# LaunchpadStepperXY.net
KiCad netlist of a schematic drawn in Altium Designer
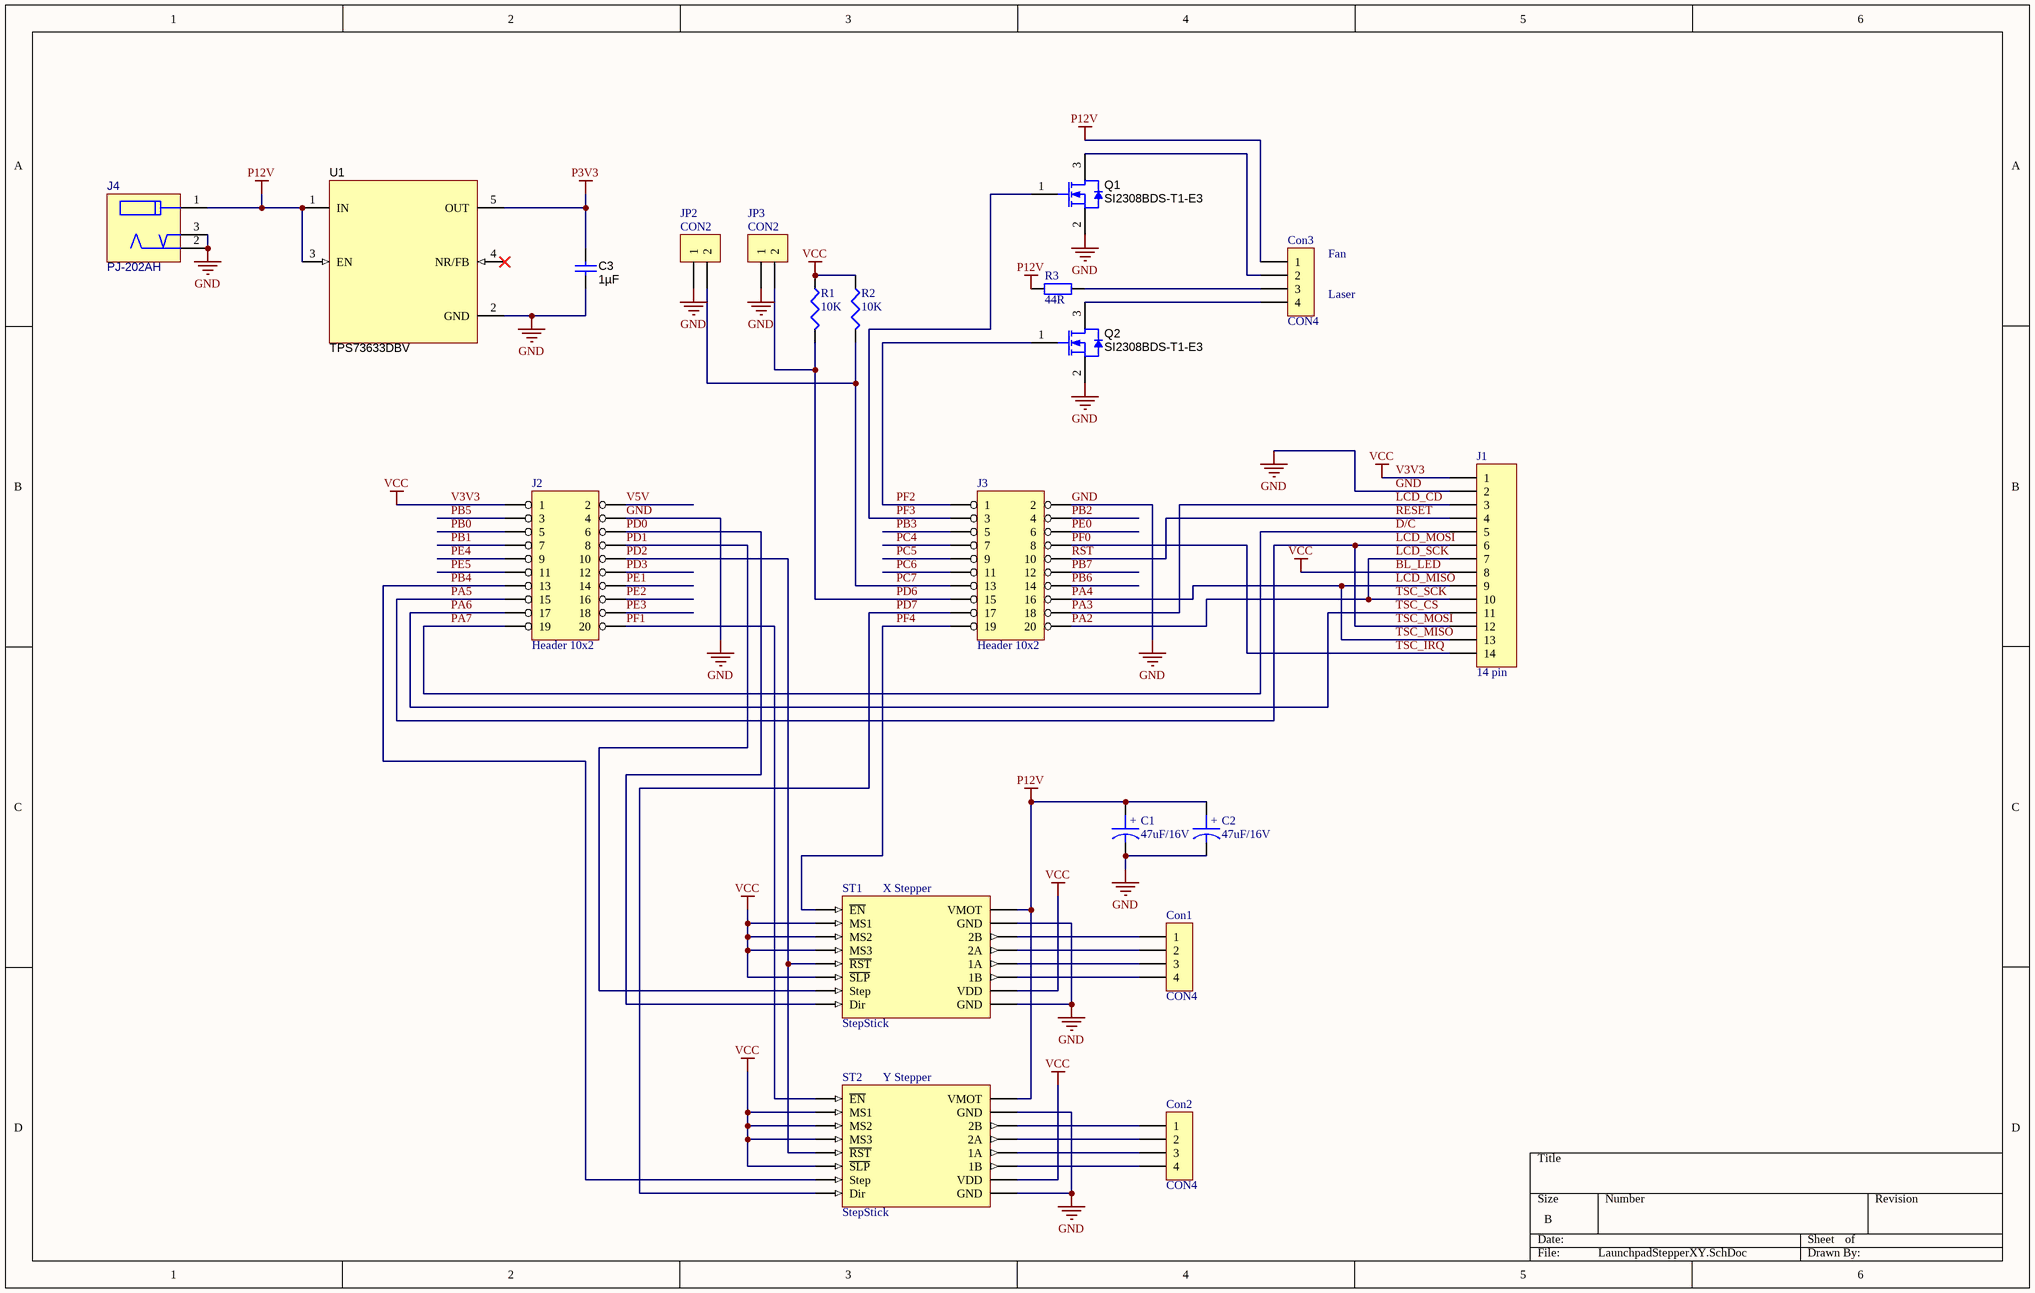
[diagram p0: LaunchpadStepperXY.SchDoc]

(export (version "E")
  (design (tool "Eeschema 10.0.6"))
  (components
    (comp (ref "C1")
      (value "47uF/16V")
      (footprint "PanasonicD")
      (description "Polarized Capacitor")
      (fields (field (name "MANUFACTURER") "Panasonic"))
      (libsource (lib "*") (part "C_POL"))
    )
    (comp (ref "C2")
      (value "47uF/16V")
      (footprint "PanasonicD")
      (description "Polarized Capacitor")
      (fields (field (name "MANUFACTURER") "Panasonic"))
      (libsource (lib "*") (part "C_POL"))
    )
    (comp (ref "C3")
      (value "UMK107AB7105KA-T")
      (footprint "0603")
      (description "CAP, CERM, 1 µF, 50 V, +/- 10%, X7R, 0603")
      (fields
        (field (name "VALUEDISPLAYED") "1µF")
        (field (name "MANUFACTURER") "Taiyo Yuden")
        (field (name "PUBLISHER") "Texas Instruments")
      )
      (libsource (lib "Capacitor_Ceramic") (part "UMK107AB7105KA-T"))
    )
    (comp (ref "Con1") (value "CON4") (footprint "SIP4") (libsource (lib "Steve") (part "CON4")))
    (comp (ref "Con2") (value "CON4") (footprint "SIP4") (libsource (lib "Steve") (part "CON4")))
    (comp (ref "Con3") (value "CON4") (footprint "SIP4") (libsource (lib "Steve") (part "CON4")))
    (comp (ref "J1")
      (value "14 pin")
      (footprint "SIP14")
      (description "Connector")
      (libsource (lib "Steve") (part "CON14"))
    )
    (comp (ref "J2") (value "Header 10x2") (footprint "IDC20") (libsource (lib "Steve") (part "Header 10x2")))
    (comp (ref "J3") (value "Header 10x2") (footprint "IDC20") (libsource (lib "Steve") (part "Header 10x2")))
    (comp (ref "J4")
      (value "PJ-202AH")
      (footprint "CONN_CUI-PJ-202AH")
      (description "Connector, DC Jack 2.1X5.5 mm, TH")
      (fields
        (field (name "MANUFACTURER") "CUI Inc.")
        (field (name "SYMBOLCREATOR") "a0799628")
        (field (name "PUBLISHER") "Texas Instruments")
      )
      (libsource (lib "Connectors_Other") (part "PJ-202AH"))
    )
    (comp (ref "JP2")
      (value "CON2")
      (footprint "SIP2")
      (description "Connector")
      (libsource (lib "Steve") (part "CON2"))
    )
    (comp (ref "JP3")
      (value "CON2")
      (footprint "SIP2")
      (description "Connector")
      (libsource (lib "Steve") (part "CON2"))
    )
    (comp (ref "Q1")
      (value "SI2308BDS-T1-E3")
      (footprint "SOT-23")
      (description "MOSFET, N-CH, 60 V, 2.3 A, SOT-23")
      (fields (field (name "MANUFACTURER") "Vishay-Siliconix") (field (name "PUBLISHER") "Texas Instruments"))
      (libsource (lib "FETs") (part "SI2308BDS-T1-E3"))
    )
    (comp (ref "Q2")
      (value "SI2308BDS-T1-E3")
      (footprint "SOT-23")
      (description "MOSFET, N-CH, 60 V, 2.3 A, SOT-23")
      (fields (field (name "MANUFACTURER") "Vishay-Siliconix") (field (name "PUBLISHER") "Texas Instruments"))
      (libsource (lib "FETs") (part "SI2308BDS-T1-E3"))
    )
    (comp (ref "R1")
      (value "10K")
      (footprint "0603")
      (description "Resistor")
      (libsource (lib "Steve") (part "RES"))
    )
    (comp (ref "R2")
      (value "10K")
      (footprint "0603")
      (description "Resistor")
      (libsource (lib "Steve") (part "RES"))
    )
    (comp (ref "R3")
      (value "44R")
      (footprint "AXIAL-0.4")
      (description "Resistor")
      (fields (field (name "PUBLISHER") "Altium Limited"))
      (libsource (lib "Miscellaneous Devices") (part "Res2"))
    )
    (comp (ref "ST1")
      (value "StepStick")
      (footprint "StepStick")
      (description "Connector")
      (libsource (lib "Steve") (part "CON14_1"))
    )
    (comp (ref "ST2")
      (value "StepStick")
      (footprint "StepStick")
      (description "Connector")
      (libsource (lib "Steve") (part "CON14_1"))
    )
    (comp (ref "U1")
      (value "TPS73633DBV")
      (footprint "DBV0005A_N")
      (description "Cap-Free, NMOS, 400mA Low-Dropout Regulator with Reverse Current Protection, DBV0005A")
      (fields
        (field (name "MANUFACTURER") "Texas Instruments")
        (field (name "SYMBOLCREATOR") "a0411947")
        (field (name "PUBLISHER") "Texas Instruments")
      )
      (libsource (lib "TI_Pre_Release") (part "TPS73633DBV"))
    )
  )
  (nets
    (net (code "1") (name "/D{slash}C") (class "Default")
      (node (ref "J1") (pin "5") (pinfunction "5_5") (pintype "passive"))
      (node (ref "J2") (pin "19") (pinfunction "19_19") (pintype "passive"))
    )
    (net (code "2") (name "/LCD_CD") (class "Default")
      (node (ref "J1") (pin "3") (pinfunction "3_3") (pintype "passive"))
      (node (ref "J3") (pin "18") (pinfunction "18_18") (pintype "passive"))
    )
    (net (code "3") (name "/LCD_MISO") (class "Default")
      (node (ref "J1") (pin "13") (pinfunction "13_13") (pintype "passive"))
      (node (ref "J1") (pin "9") (pinfunction "9_9") (pintype "passive"))
      (node (ref "J3") (pin "16") (pinfunction "16_16") (pintype "passive"))
    )
    (net (code "4") (name "/LCD_MOSI") (class "Default")
      (node (ref "J1") (pin "12") (pinfunction "12_12") (pintype "passive"))
      (node (ref "J1") (pin "6") (pinfunction "6_6") (pintype "passive"))
      (node (ref "J2") (pin "15") (pinfunction "15_15") (pintype "passive"))
    )
    (net (code "5") (name "/LCD_SCK") (class "Default")
      (node (ref "J1") (pin "10") (pinfunction "10_10") (pintype "passive"))
      (node (ref "J1") (pin "7") (pinfunction "7_7") (pintype "passive"))
      (node (ref "J3") (pin "20") (pinfunction "20_20") (pintype "passive"))
    )
    (net (code "6") (name "/PA6") (class "Default")
      (node (ref "J1") (pin "11") (pinfunction "11_11") (pintype "passive"))
      (node (ref "J2") (pin "17") (pinfunction "17_17") (pintype "passive"))
    )
    (net (code "7") (name "/PB0") (class "Default")
      (node (ref "J2") (pin "5") (pinfunction "5_5") (pintype "passive"))
    )
    (net (code "8") (name "/PB1") (class "Default")
      (node (ref "J2") (pin "7") (pinfunction "7_7") (pintype "passive"))
    )
    (net (code "9") (name "/PB2") (class "Default")
      (node (ref "J3") (pin "4") (pinfunction "4_4") (pintype "passive"))
    )
    (net (code "10") (name "/PB3") (class "Default")
      (node (ref "J3") (pin "5") (pinfunction "5_5") (pintype "passive"))
    )
    (net (code "11") (name "/PB4") (class "Default")
      (node (ref "J2") (pin "13") (pinfunction "13_13") (pintype "passive"))
      (node (ref "ST2") (pin "7") (pinfunction "Step_7") (pintype "input"))
    )
    (net (code "12") (name "/PB5") (class "Default")
      (node (ref "J2") (pin "3") (pinfunction "3_3") (pintype "passive"))
    )
    (net (code "13") (name "/PB6") (class "Default")
      (node (ref "J3") (pin "14") (pinfunction "14_14") (pintype "passive"))
    )
    (net (code "14") (name "/PB7") (class "Default")
      (node (ref "J3") (pin "12") (pinfunction "12_12") (pintype "passive"))
    )
    (net (code "15") (name "/PC4") (class "Default")
      (node (ref "J3") (pin "7") (pinfunction "7_7") (pintype "passive"))
    )
    (net (code "16") (name "/PC5") (class "Default")
      (node (ref "J3") (pin "9") (pinfunction "9_9") (pintype "passive"))
    )
    (net (code "17") (name "/PC6") (class "Default")
      (node (ref "J3") (pin "11") (pinfunction "11_11") (pintype "passive"))
    )
    (net (code "18") (name "/PC7") (class "Default")
      (node (ref "J3") (pin "13") (pinfunction "13_13") (pintype "passive"))
      (node (ref "JP2") (pin "2") (pinfunction "2_2") (pintype "passive"))
      (node (ref "R2") (pin "2") (pinfunction "2_2") (pintype "passive"))
    )
    (net (code "19") (name "/PD0") (class "Default")
      (node (ref "J2") (pin "6") (pinfunction "6_6") (pintype "passive"))
      (node (ref "ST1") (pin "8") (pinfunction "Dir_8") (pintype "input"))
    )
    (net (code "20") (name "/PD1") (class "Default")
      (node (ref "J2") (pin "8") (pinfunction "8_8") (pintype "passive"))
      (node (ref "ST1") (pin "7") (pinfunction "Step_7") (pintype "input"))
    )
    (net (code "21") (name "/PD2") (class "Default")
      (node (ref "J2") (pin "10") (pinfunction "10_10") (pintype "passive"))
      (node (ref "ST1") (pin "5") (pinfunction "~{RST}_5") (pintype "input"))
      (node (ref "ST2") (pin "5") (pinfunction "~{RST}_5") (pintype "input"))
    )
    (net (code "22") (name "/PD3") (class "Default")
      (node (ref "J2") (pin "12") (pinfunction "12_12") (pintype "passive"))
    )
    (net (code "23") (name "/PD6") (class "Default")
      (node (ref "J3") (pin "15") (pinfunction "15_15") (pintype "passive"))
      (node (ref "JP3") (pin "2") (pinfunction "2_2") (pintype "passive"))
      (node (ref "R1") (pin "2") (pinfunction "2_2") (pintype "passive"))
    )
    (net (code "24") (name "/PD7") (class "Default")
      (node (ref "J3") (pin "17") (pinfunction "17_17") (pintype "passive"))
      (node (ref "ST2") (pin "8") (pinfunction "Dir_8") (pintype "input"))
    )
    (net (code "25") (name "/PE0") (class "Default")
      (node (ref "J3") (pin "6") (pinfunction "6_6") (pintype "passive"))
    )
    (net (code "26") (name "/PE1") (class "Default")
      (node (ref "J2") (pin "14") (pinfunction "14_14") (pintype "passive"))
    )
    (net (code "27") (name "/PE2") (class "Default")
      (node (ref "J2") (pin "16") (pinfunction "16_16") (pintype "passive"))
    )
    (net (code "28") (name "/PE3") (class "Default")
      (node (ref "J2") (pin "18") (pinfunction "18_18") (pintype "passive"))
    )
    (net (code "29") (name "/PE4") (class "Default")
      (node (ref "J2") (pin "9") (pinfunction "9_9") (pintype "passive"))
    )
    (net (code "30") (name "/PE5") (class "Default")
      (node (ref "J2") (pin "11") (pinfunction "11_11") (pintype "passive"))
    )
    (net (code "31") (name "/PF0") (class "Default")
      (node (ref "J1") (pin "14") (pinfunction "14_14") (pintype "passive"))
      (node (ref "J3") (pin "8") (pinfunction "8_8") (pintype "passive"))
    )
    (net (code "32") (name "/PF1") (class "Default")
      (node (ref "J2") (pin "20") (pinfunction "20_20") (pintype "passive"))
      (node (ref "ST2") (pin "1") (pinfunction "~{EN}_1") (pintype "input"))
    )
    (net (code "33") (name "/PF2") (class "Default")
      (node (ref "J3") (pin "1") (pinfunction "1_1") (pintype "passive"))
      (node (ref "Q2") (pin "1") (pinfunction "G_1") (pintype "passive"))
    )
    (net (code "34") (name "/PF3") (class "Default")
      (node (ref "J3") (pin "3") (pinfunction "3_3") (pintype "passive"))
      (node (ref "Q1") (pin "1") (pinfunction "G_1") (pintype "passive"))
    )
    (net (code "35") (name "/PF4") (class "Default")
      (node (ref "J3") (pin "19") (pinfunction "19_19") (pintype "passive"))
      (node (ref "ST1") (pin "1") (pinfunction "~{EN}_1") (pintype "input"))
    )
    (net (code "36") (name "/V5V") (class "Default")
      (node (ref "J2") (pin "2") (pinfunction "2_2") (pintype "passive"))
    )
    (net (code "37") (name "/~{RESET}") (class "Default")
      (node (ref "J1") (pin "4") (pinfunction "4_4") (pintype "passive"))
      (node (ref "J3") (pin "10") (pinfunction "10_10") (pintype "passive"))
    )
    (net (code "38") (name "GND") (class "Default")
      (node (ref "C1") (pin "2") (pinfunction "2_2") (pintype "passive"))
      (node (ref "C2") (pin "2") (pinfunction "2_2") (pintype "passive"))
      (node (ref "C3") (pin "2") (pinfunction "2_2") (pintype "passive"))
      (node (ref "J1") (pin "2") (pinfunction "2_2") (pintype "passive"))
      (node (ref "J2") (pin "4") (pinfunction "4_4") (pintype "passive"))
      (node (ref "J3") (pin "2") (pinfunction "2_2") (pintype "passive"))
      (node (ref "J4") (pin "2") (pinfunction "2_2") (pintype "passive"))
      (node (ref "J4") (pin "3") (pinfunction "3_3") (pintype "passive"))
      (node (ref "JP2") (pin "1") (pinfunction "1_1") (pintype "passive"))
      (node (ref "JP3") (pin "1") (pinfunction "1_1") (pintype "passive"))
      (node (ref "Q1") (pin "2") (pinfunction "S_2") (pintype "passive"))
      (node (ref "Q2") (pin "2") (pinfunction "S_2") (pintype "passive"))
      (node (ref "ST1") (pin "15") (pinfunction "GND_15") (pintype "power_in"))
      (node (ref "ST1") (pin "9") (pinfunction "GND_9") (pintype "power_in"))
      (node (ref "ST2") (pin "15") (pinfunction "GND_15") (pintype "power_in"))
      (node (ref "ST2") (pin "9") (pinfunction "GND_9") (pintype "power_in"))
      (node (ref "U1") (pin "2") (pinfunction "GND_2") (pintype "power_in"))
    )
    (net (code "39") (name "Net-(Con3-Pad3)") (class "Default")
      (node (ref "Con3") (pin "3") (pinfunction "3_3") (pintype "passive"))
      (node (ref "R3") (pin "1") (pinfunction "1_1") (pintype "passive"))
    )
    (net (code "40") (name "Net-(Q1-D)") (class "Default")
      (node (ref "Con3") (pin "2") (pinfunction "2_2") (pintype "passive"))
      (node (ref "Q1") (pin "3") (pinfunction "D_3") (pintype "passive"))
    )
    (net (code "41") (name "Net-(Q2-D)") (class "Default")
      (node (ref "Con3") (pin "4") (pinfunction "4_4") (pintype "passive"))
      (node (ref "Q2") (pin "3") (pinfunction "D_3") (pintype "passive"))
    )
    (net (code "42") (name "Net-(ST1-1A)") (class "Default")
      (node (ref "Con1") (pin "3") (pinfunction "3_3") (pintype "passive"))
      (node (ref "ST1") (pin "12") (pinfunction "1A_12") (pintype "output"))
    )
    (net (code "43") (name "Net-(ST1-1B)") (class "Default")
      (node (ref "Con1") (pin "4") (pinfunction "4_4") (pintype "passive"))
      (node (ref "ST1") (pin "11") (pinfunction "1B_11") (pintype "output"))
    )
    (net (code "44") (name "Net-(ST1-2A)") (class "Default")
      (node (ref "Con1") (pin "2") (pinfunction "2_2") (pintype "passive"))
      (node (ref "ST1") (pin "13") (pinfunction "2A_13") (pintype "output"))
    )
    (net (code "45") (name "Net-(ST1-2B)") (class "Default")
      (node (ref "Con1") (pin "1") (pinfunction "1_1") (pintype "passive"))
      (node (ref "ST1") (pin "14") (pinfunction "2B_14") (pintype "output"))
    )
    (net (code "46") (name "Net-(ST2-1A)") (class "Default")
      (node (ref "Con2") (pin "3") (pinfunction "3_3") (pintype "passive"))
      (node (ref "ST2") (pin "12") (pinfunction "1A_12") (pintype "output"))
    )
    (net (code "47") (name "Net-(ST2-1B)") (class "Default")
      (node (ref "Con2") (pin "4") (pinfunction "4_4") (pintype "passive"))
      (node (ref "ST2") (pin "11") (pinfunction "1B_11") (pintype "output"))
    )
    (net (code "48") (name "Net-(ST2-2A)") (class "Default")
      (node (ref "Con2") (pin "2") (pinfunction "2_2") (pintype "passive"))
      (node (ref "ST2") (pin "13") (pinfunction "2A_13") (pintype "output"))
    )
    (net (code "49") (name "Net-(ST2-2B)") (class "Default")
      (node (ref "Con2") (pin "1") (pinfunction "1_1") (pintype "passive"))
      (node (ref "ST2") (pin "14") (pinfunction "2B_14") (pintype "output"))
    )
    (net (code "50") (name "P3V3") (class "Default")
      (node (ref "C3") (pin "1") (pinfunction "1_1") (pintype "passive"))
      (node (ref "U1") (pin "5") (pinfunction "OUT_5") (pintype "power_in"))
    )
    (net (code "51") (name "P12V") (class "Default")
      (node (ref "C1") (pin "1") (pinfunction "1_1") (pintype "passive"))
      (node (ref "C2") (pin "1") (pinfunction "1_1") (pintype "passive"))
      (node (ref "Con3") (pin "1") (pinfunction "1_1") (pintype "passive"))
      (node (ref "J4") (pin "1") (pinfunction "1_1") (pintype "passive"))
      (node (ref "R3") (pin "2") (pinfunction "2_2") (pintype "passive"))
      (node (ref "ST1") (pin "16") (pinfunction "VMOT_16") (pintype "power_in"))
      (node (ref "ST2") (pin "16") (pinfunction "VMOT_16") (pintype "power_in"))
      (node (ref "U1") (pin "1") (pinfunction "IN_1") (pintype "power_in"))
      (node (ref "U1") (pin "3") (pinfunction "EN_3") (pintype "input"))
    )
    (net (code "52") (name "VCC") (class "Default")
      (node (ref "J1") (pin "1") (pinfunction "1_1") (pintype "passive"))
      (node (ref "J1") (pin "8") (pinfunction "8_8") (pintype "passive"))
      (node (ref "J2") (pin "1") (pinfunction "1_1") (pintype "passive"))
      (node (ref "R1") (pin "1") (pinfunction "1_1") (pintype "passive"))
      (node (ref "R2") (pin "1") (pinfunction "1_1") (pintype "passive"))
      (node (ref "ST1") (pin "10") (pinfunction "VDD_10") (pintype "power_in"))
      (node (ref "ST1") (pin "2") (pinfunction "MS1_2") (pintype "input"))
      (node (ref "ST1") (pin "3") (pinfunction "MS2_3") (pintype "input"))
      (node (ref "ST1") (pin "4") (pinfunction "MS3_4") (pintype "input"))
      (node (ref "ST1") (pin "6") (pinfunction "~{SLP}_6") (pintype "input"))
      (node (ref "ST2") (pin "10") (pinfunction "VDD_10") (pintype "power_in"))
      (node (ref "ST2") (pin "2") (pinfunction "MS1_2") (pintype "input"))
      (node (ref "ST2") (pin "3") (pinfunction "MS2_3") (pintype "input"))
      (node (ref "ST2") (pin "4") (pinfunction "MS3_4") (pintype "input"))
      (node (ref "ST2") (pin "6") (pinfunction "~{SLP}_6") (pintype "input"))
    )
    (net (code "53") (name "unconnected-(U1-NR{slash}FB-Pad4)") (class "Default")
      (node (ref "U1") (pin "4") (pinfunction "NR/FB_4") (pintype "input+no_connect"))
    )
  )
)
